# LM2596_Power_Supply_Adjustable.net
KiCad netlist of a schematic drawn in Altium Designer
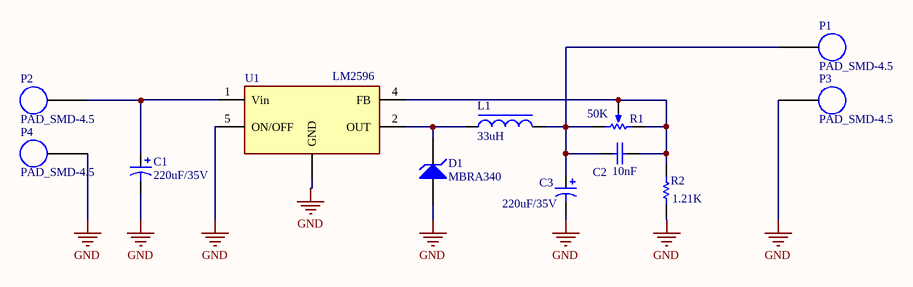
[diagram p0: LM2596_Power_Supply_Adjustable.SchDoc]

(export (version "E")
  (design (tool "Eeschema 10.0.6"))
  (components
    (comp (ref "C1")
      (value "220uF/35V")
      (footprint "Cap_Al_SMD_C6_6.6x6.6mm")
      (description "Polarized Capacitor")
      (libsource (lib "Basic Library") (part "CP"))
    )
    (comp (ref "C2")
      (value "10nF")
      (footprint "C2012[0805]")
      (description "Capacitor")
      (libsource (lib "Basic Library") (part "C"))
    )
    (comp (ref "C3")
      (value "220uF/35V")
      (footprint "Cap_Al_SMD_C6_6.6x6.6mm")
      (description "Polarized Capacitor")
      (libsource (lib "Basic Library") (part "CP"))
    )
    (comp (ref "D1")
      (value "MBRA340")
      (footprint "DO214AC")
      (description "Zener Diode")
      (libsource (lib "Basic Library") (part "D Zener"))
    )
    (comp (ref "L1")
      (value "33uH")
      (footprint "Inductor-744770133")
      (description "Inductor")
      (libsource (lib "Basic Library") (part "L"))
    )
    (comp (ref "P1")
      (value "PAD_SMD-4.5")
      (footprint "PAD_SMD_4.5")
      (libsource (lib "Basic Library") (part "PAD_SMD-4.5"))
    )
    (comp (ref "P2")
      (value "PAD_SMD-4.5")
      (footprint "PAD_SMD_4.5")
      (libsource (lib "Basic Library") (part "PAD_SMD-4.5"))
    )
    (comp (ref "P3")
      (value "PAD_SMD-4.5")
      (footprint "PAD_SMD_4.5")
      (libsource (lib "Basic Library") (part "PAD_SMD-4.5"))
    )
    (comp (ref "P4")
      (value "PAD_SMD-4.5")
      (footprint "PAD_SMD_4.5")
      (libsource (lib "Basic Library") (part "PAD_SMD-4.5"))
    )
    (comp (ref "R1")
      (value "50K")
      (footprint "VR1")
      (description "Potentiometer")
      (fields (field (name "PUBLISHER") "Altium Limited"))
      (libsource (lib "Miscellaneous Devices") (part "RPot"))
    )
    (comp (ref "R2")
      (value "1.21K")
      (footprint "R2012[0805]")
      (description "Resistor")
      (libsource (lib "Basic Library") (part "R"))
    )
    (comp (ref "U1") (value "LM2596") (footprint "3961-02") (libsource (lib "Basic Library") (part "LM2596")))
  )
  (nets
    (net (code "1") (name "GND") (class "Default")
      (node (ref "C1") (pin "2") (pinfunction "2_2") (pintype "passive"))
      (node (ref "C3") (pin "2") (pinfunction "2_2") (pintype "passive"))
      (node (ref "D1") (pin "1") (pinfunction "A_1") (pintype "passive"))
      (node (ref "P3") (pin "1") (pinfunction "1_1") (pintype "passive"))
      (node (ref "P4") (pin "1") (pinfunction "1_1") (pintype "passive"))
      (node (ref "R2") (pin "1") (pinfunction "1_1") (pintype "passive"))
      (node (ref "U1") (pin "3") (pinfunction "GND_3") (pintype "passive"))
      (node (ref "U1") (pin "5") (pinfunction "ON/OFF_5") (pintype "passive"))
    )
    (net (code "2") (name "Net-(D1-K)") (class "Default")
      (node (ref "D1") (pin "2") (pinfunction "K_2") (pintype "passive"))
      (node (ref "L1") (pin "1") (pinfunction "1_1") (pintype "passive"))
      (node (ref "U1") (pin "2") (pinfunction "OUT_2") (pintype "passive"))
    )
    (net (code "3") (name "Net-(R1-BOT)") (class "Default")
      (node (ref "C2") (pin "1") (pinfunction "1_1") (pintype "passive"))
      (node (ref "C3") (pin "1") (pinfunction "1_1") (pintype "passive"))
      (node (ref "L1") (pin "2") (pinfunction "2_2") (pintype "passive"))
      (node (ref "P1") (pin "1") (pinfunction "1_1") (pintype "passive"))
      (node (ref "R1") (pin "2") (pinfunction "BOT_2") (pintype "passive"))
    )
    (net (code "4") (name "Net-(R1-TAP)") (class "Default")
      (node (ref "C2") (pin "2") (pinfunction "2_2") (pintype "passive"))
      (node (ref "R1") (pin "1") (pinfunction "TOP_1") (pintype "passive"))
      (node (ref "R1") (pin "3") (pinfunction "TAP_3") (pintype "passive"))
      (node (ref "R2") (pin "2") (pinfunction "2_2") (pintype "passive"))
      (node (ref "U1") (pin "4") (pinfunction "FB_4") (pintype "passive"))
    )
    (net (code "5") (name "Net-(U1-Vin)") (class "Default")
      (node (ref "C1") (pin "1") (pinfunction "1_1") (pintype "passive"))
      (node (ref "P2") (pin "1") (pinfunction "1_1") (pintype "passive"))
      (node (ref "U1") (pin "1") (pinfunction "Vin_1") (pintype "passive"))
    )
  )
)
